# Sheet1.net
KiCad netlist of a schematic drawn in Altium Designer
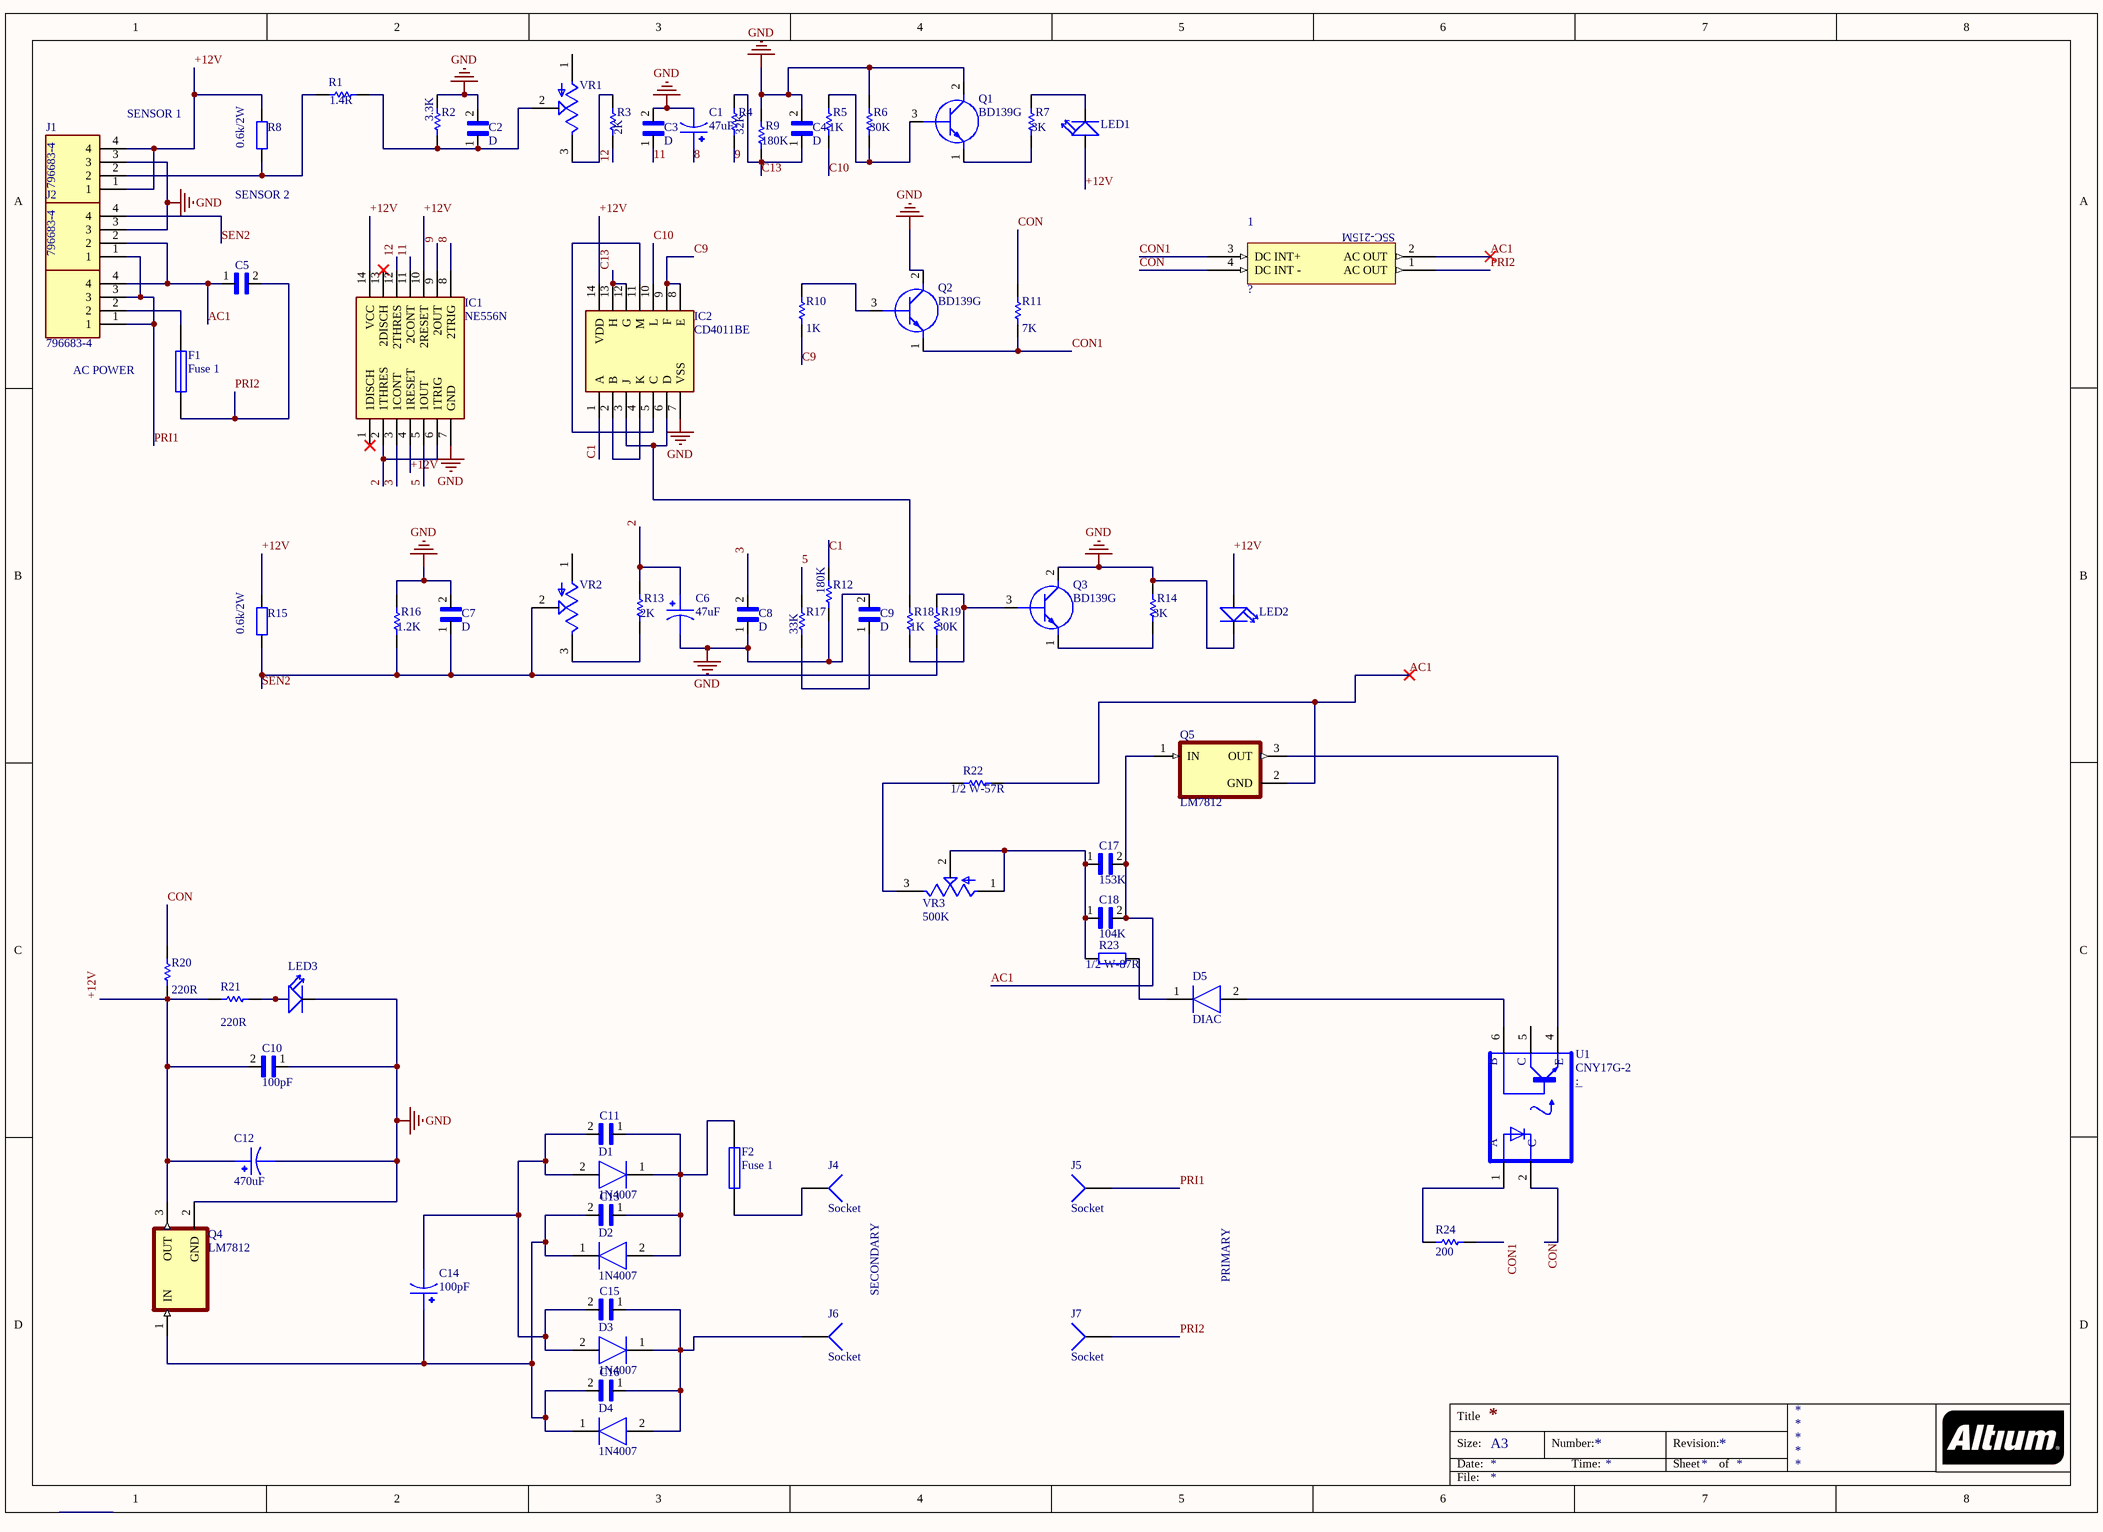
[diagram p0: Sheet1.SchDoc]

(export (version "E")
  (design (tool "Eeschema 10.0.6"))
  (components
    (comp (ref "1")
      (value "?")
      (footprint "PCBComponent_1")
      (libsource (lib "s5C-215M") (part "Component_1"))
    )
    (comp (ref "C1")
      (value "47uF")
      (footprint "CAPPRD500W60D1330H2700")
      (description "4700ÂµF 10V Aluminum Electrolytic Capacitors Radial, Can 98.8mOhm @ 120Hz 2000 Hrs @ 85Â°C")
      (fields (field (name "MP") "478CKS010M") (field (name "MF") "Illinois Capacitor"))
      (libsource (lib "new polar CAP 3D") (part "478CKS010M"))
    )
    (comp (ref "C2")
      (value "D")
      (footprint "CAP_DE21XSA100KN3AY02F")
      (fields (field (name "MP") "DE21XSA100KN3AY02F"))
      (libsource (lib "nonpolar capacitor square 3D") (part "DE21XSA100KN3AY02F"))
    )
    (comp (ref "C3")
      (value "D")
      (footprint "CAP_DE21XSA100KN3AY02F")
      (fields (field (name "MP") "DE21XSA100KN3AY02F"))
      (libsource (lib "nonpolar capacitor square 3D") (part "DE21XSA100KN3AY02F"))
    )
    (comp (ref "C4")
      (value "D")
      (footprint "CAP_DE21XSA100KN3AY02F")
      (fields (field (name "MP") "DE21XSA100KN3AY02F"))
      (libsource (lib "nonpolar capacitor square 3D") (part "DE21XSA100KN3AY02F"))
    )
    (comp (ref "C5")
      (value "~")
      (footprint "CAP_DE21XSA100KN3AY02F")
      (fields (field (name "MP") "DE21XSA100KN3AY02F"))
      (libsource (lib "nonpolar capacitor round 3D") (part "DE21XSA100KN3AY02F"))
    )
    (comp (ref "C6")
      (value "47uF")
      (footprint "CAPPRD500W60D1330H2700")
      (description "4700ÂµF 10V Aluminum Electrolytic Capacitors Radial, Can 98.8mOhm @ 120Hz 2000 Hrs @ 85Â°C")
      (fields (field (name "MP") "478CKS010M") (field (name "MF") "Illinois Capacitor"))
      (libsource (lib "") (part "478CKS010M_1"))
    )
    (comp (ref "C7")
      (value "D")
      (footprint "CAP_DE21XSA100KN3AY02F")
      (fields (field (name "MP") "DE21XSA100KN3AY02F"))
      (libsource (lib "nonpolar capacitor square 3D") (part "DE21XSA100KN3AY02F"))
    )
    (comp (ref "C8")
      (value "D")
      (footprint "CAP_DE21XSA100KN3AY02F")
      (fields (field (name "MP") "DE21XSA100KN3AY02F"))
      (libsource (lib "nonpolar capacitor square 3D") (part "DE21XSA100KN3AY02F"))
    )
    (comp (ref "C9")
      (value "D")
      (footprint "CAP_DE21XSA100KN3AY02F")
      (fields (field (name "MP") "DE21XSA100KN3AY02F"))
      (libsource (lib "nonpolar capacitor square 3D") (part "DE21XSA100KN3AY02F"))
    )
    (comp (ref "C10")
      (value "100pF")
      (footprint "CAP_DE21XSA100KN3AY02F")
      (fields (field (name "MP") "DE21XSA100KN3AY02F"))
      (libsource (lib "") (part "DE21XSA100KN3AY02F_1"))
    )
    (comp (ref "C11")
      (value "~")
      (footprint "CAP_DE21XSA100KN3AY02F")
      (fields (field (name "MP") "DE21XSA100KN3AY02F"))
      (libsource (lib "") (part "DE21XSA100KN3AY02F_1"))
    )
    (comp (ref "C12")
      (value "470uF")
      (footprint "CAPPRD500W60D1330H2700")
      (description "4700ÂµF 10V Aluminum Electrolytic Capacitors Radial, Can 98.8mOhm @ 120Hz 2000 Hrs @ 85Â°C")
      (fields (field (name "MP") "478CKS010M") (field (name "MF") "Illinois Capacitor"))
      (libsource (lib "CAP") (part "478CKS010M"))
    )
    (comp (ref "C13")
      (value "~")
      (footprint "CAP_DE21XSA100KN3AY02F")
      (fields (field (name "MP") "DE21XSA100KN3AY02F"))
      (libsource (lib "") (part "DE21XSA100KN3AY02F_1"))
    )
    (comp (ref "C14")
      (value "100pF")
      (footprint "CAPPRD500W60D1330H2700")
      (description "4700ÂµF 10V Aluminum Electrolytic Capacitors Radial, Can 98.8mOhm @ 120Hz 2000 Hrs @ 85Â°C")
      (fields (field (name "MP") "478CKS010M") (field (name "MF") "Illinois Capacitor"))
      (libsource (lib "new polar CAP 3D") (part "478CKS010M"))
    )
    (comp (ref "C15")
      (value "~")
      (footprint "CAP_DE21XSA100KN3AY02F")
      (fields (field (name "MP") "DE21XSA100KN3AY02F"))
      (libsource (lib "") (part "DE21XSA100KN3AY02F_1"))
    )
    (comp (ref "C16")
      (value "~")
      (footprint "CAP_DE21XSA100KN3AY02F")
      (fields (field (name "MP") "DE21XSA100KN3AY02F"))
      (libsource (lib "") (part "DE21XSA100KN3AY02F_1"))
    )
    (comp (ref "C17")
      (value "153K")
      (footprint "CAP_DE21XSA100KN3AY02F")
      (fields (field (name "MP") "DE21XSA100KN3AY02F"))
      (libsource (lib "") (part "DE21XSA100KN3AY02F_1"))
    )
    (comp (ref "C18")
      (value "104K")
      (footprint "CAP_DE21XSA100KN3AY02F")
      (fields (field (name "MP") "DE21XSA100KN3AY02F"))
      (libsource (lib "") (part "DE21XSA100KN3AY02F_1"))
    )
    (comp (ref "D1")
      (value "1N4007")
      (footprint "DIOAD1138W56L406D183")
      (description "Diode")
      (fields (field (name "MANUFACTURER_PART_NUMBER") "1N4678 (DO35)"))
      (libsource (lib "diode with 3d model") (part "1N4678__DO35_"))
    )
    (comp (ref "D2")
      (value "1N4007")
      (footprint "DIOAD1138W56L406D183")
      (description "Diode")
      (fields (field (name "MANUFACTURER_PART_NUMBER") "1N4678 (DO35)"))
      (libsource (lib "diode with 3d model") (part "1N4678__DO35_"))
    )
    (comp (ref "D3")
      (value "1N4007")
      (footprint "DIOAD1138W56L406D183")
      (description "Diode")
      (fields (field (name "MANUFACTURER_PART_NUMBER") "1N4678 (DO35)"))
      (libsource (lib "diode with 3d model") (part "1N4678__DO35_"))
    )
    (comp (ref "D4")
      (value "1N4007")
      (footprint "DIOAD1138W56L406D183")
      (description "Diode")
      (fields (field (name "MANUFACTURER_PART_NUMBER") "1N4678 (DO35)"))
      (libsource (lib "diode with 3d model") (part "1N4678__DO35_"))
    )
    (comp (ref "D5")
      (value "DIAC")
      (footprint "DIOAD1138W56L406D183")
      (description "Diode")
      (fields (field (name "MANUFACTURER_PART_NUMBER") "1N4678 (DO35)"))
      (libsource (lib "diode with 3d model") (part "1N4678__DO35_"))
    )
    (comp (ref "F1")
      (value "Fuse 1")
      (footprint "PIN-W2/E2.8")
      (description "Fuse")
      (fields (field (name "PUBLISHER") "Altium Limited"))
      (libsource (lib "Miscellaneous Devices") (part "Fuse 1"))
    )
    (comp (ref "F2")
      (value "Fuse 1")
      (footprint "PIN-W2/E2.8")
      (description "Fuse")
      (fields (field (name "PUBLISHER") "Altium Limited"))
      (libsource (lib "Miscellaneous Devices") (part "Fuse 1"))
    )
    (comp (ref "IC1")
      (value "NE556N")
      (footprint "DIP794W53P254L1930H508Q14N")
      (description "Integrated Circuit")
      (fields (field (name "MOUSER PART NUMBER") "595-NE556N"))
      (libsource (lib "NE556") (part "NE556N"))
    )
    (comp (ref "IC2")
      (value "CD4011BE")
      (footprint "SamacSys:DIP794W53P254L1930H508Q14N")
      (description "Integrated Circuit")
      (fields (field (name "MOUSER PART NUMBER") "595-CD4011BE"))
      (libsource (lib "CD4011") (part "CD4011BE"))
    )
    (comp (ref "J1")
      (value "796683-4")
      (footprint "TE_796683-4")
      (description "TERMI-BLOK PCB MOUNT 90 4P.")
      (fields (field (name "MF") "TE Connectivity"))
      (libsource (lib "4pin terminal 3D") (part "796683-4"))
    )
    (comp (ref "J2")
      (value "796683-4")
      (footprint "TE_796683-4")
      (description "TERMI-BLOK PCB MOUNT 90 4P.")
      (fields (field (name "MF") "TE Connectivity"))
      (libsource (lib "4pin terminal 3D") (part "796683-4"))
    )
    (comp (ref "J3")
      (value "796683-4")
      (footprint "TE_796683-4")
      (description "TERMI-BLOK PCB MOUNT 90 4P.")
      (fields (field (name "MF") "TE Connectivity"))
      (libsource (lib "4pin terminal 3D") (part "796683-4"))
    )
    (comp (ref "J4")
      (value "Socket")
      (footprint "PIN1")
      (fields (field (name "PUBLISHER") "Altium Limited"))
      (libsource (lib "Miscellaneous Connectors") (part "Socket"))
    )
    (comp (ref "J5")
      (value "Socket")
      (footprint "PIN1")
      (fields (field (name "PUBLISHER") "Altium Limited"))
      (libsource (lib "Miscellaneous Connectors") (part "Socket"))
    )
    (comp (ref "J6")
      (value "Socket")
      (footprint "PIN1")
      (fields (field (name "PUBLISHER") "Altium Limited"))
      (libsource (lib "Miscellaneous Connectors") (part "Socket"))
    )
    (comp (ref "J7")
      (value "Socket")
      (footprint "PIN1")
      (fields (field (name "PUBLISHER") "Altium Limited"))
      (libsource (lib "Miscellaneous Connectors") (part "Socket"))
    )
    (comp (ref "LED1")
      (value "~")
      (footprint "LED2-2.54-D10MM")
      (description "DIP LED Green-Vaporous Green-10mm")
      (fields (field (name "MF") "Chengguangxing") (field (name "MP") "G1004DC"))
      (libsource (lib "LED 3D") (part "DIP-LED-GREEN-VAPOROUS-GREEN-10MM(2P-D10MM)"))
    )
    (comp (ref "LED2")
      (value "~")
      (footprint "LED2-2.54-D10MM")
      (description "DIP LED Green-Vaporous Green-10mm")
      (fields (field (name "MF") "Chengguangxing") (field (name "MP") "G1004DC"))
      (libsource (lib "LED 3D") (part "DIP-LED-GREEN-VAPOROUS-GREEN-10MM(2P-D10MM)"))
    )
    (comp (ref "LED3")
      (value "~")
      (footprint "LED2-2.54-D10MM")
      (description "DIP LED Green-Vaporous Green-10mm")
      (fields (field (name "MF") "Chengguangxing") (field (name "MP") "G1004DC"))
      (libsource (lib "LED 3D") (part "DIP-LED-GREEN-VAPOROUS-GREEN-10MM(2P-D10MM)"))
    )
    (comp (ref "Q1")
      (value "BD139G")
      (footprint "TO229P300X760X1364-3P")
      (description "Transistor BJT NPN")
      (fields (field (name "MOUSER PART NUMBER") "863-BD139G"))
      (libsource (lib "BD139 NPN transistor") (part "BD139G"))
    )
    (comp (ref "Q2")
      (value "BD139G")
      (footprint "TO229P300X760X1364-3P")
      (description "Transistor BJT NPN")
      (fields (field (name "MOUSER PART NUMBER") "863-BD139G"))
      (libsource (lib "BD139 NPN transistor") (part "BD139G"))
    )
    (comp (ref "Q3")
      (value "BD139G")
      (footprint "TO229P300X760X1364-3P")
      (description "Transistor BJT NPN")
      (fields (field (name "MOUSER PART NUMBER") "863-BD139G"))
      (libsource (lib "BD139 NPN transistor") (part "BD139G"))
    )
    (comp (ref "Q4")
      (value "LM7812")
      (footprint "TO254P1054X470X2600-3")
      (description "Linear Voltage Regulator IC 1 Output 1A TO-220-3")
      (fields (field (name "MP") "LM7805CT") (field (name "MF") "ON Semiconductor"))
      (libsource (lib "") (part "LM7805CT/NOPB_1"))
    )
    (comp (ref "Q5")
      (value "LM7812")
      (footprint "TO254P1054X470X2600-3")
      (description "Linear Voltage Regulator IC 1 Output 1A TO-220-3")
      (fields (field (name "MP") "LM7805CT") (field (name "MF") "ON Semiconductor"))
      (libsource (lib "LM7805 3D") (part "LM7805CT/NOPB"))
    )
    (comp (ref "R1")
      (value "1.4R")
      (footprint "AXIAL-0.5")
      (description "Semiconductor Resistor")
      (fields (field (name "PUBLISHER") "Altium Limited"))
      (libsource (lib "Miscellaneous Devices") (part "Res Semi"))
    )
    (comp (ref "R2")
      (value "3.3K")
      (footprint "AXIAL-0.5")
      (description "Semiconductor Resistor")
      (fields (field (name "PUBLISHER") "Altium Limited"))
      (libsource (lib "Miscellaneous Devices") (part "Res Semi"))
    )
    (comp (ref "R3")
      (value "2K")
      (footprint "AXIAL-0.5")
      (description "Semiconductor Resistor")
      (fields (field (name "PUBLISHER") "Altium Limited"))
      (libsource (lib "Miscellaneous Devices") (part "Res Semi"))
    )
    (comp (ref "R4")
      (value "32K")
      (footprint "AXIAL-0.5")
      (description "Semiconductor Resistor")
      (fields (field (name "PUBLISHER") "Altium Limited"))
      (libsource (lib "Miscellaneous Devices") (part "Res Semi"))
    )
    (comp (ref "R5")
      (value "1K")
      (footprint "AXIAL-0.5")
      (description "Semiconductor Resistor")
      (fields (field (name "PUBLISHER") "Altium Limited"))
      (libsource (lib "Miscellaneous Devices") (part "Res Semi"))
    )
    (comp (ref "R6")
      (value "30K")
      (footprint "AXIAL-0.5")
      (description "Semiconductor Resistor")
      (fields (field (name "PUBLISHER") "Altium Limited"))
      (libsource (lib "Miscellaneous Devices") (part "Res Semi"))
    )
    (comp (ref "R7")
      (value "3K")
      (footprint "AXIAL-0.5")
      (description "Semiconductor Resistor")
      (fields (field (name "PUBLISHER") "Altium Limited"))
      (libsource (lib "Miscellaneous Devices") (part "Res Semi"))
    )
    (comp (ref "R8")
      (value "0.6k/2W")
      (footprint "AXIAL-0.4")
      (description "Resistor")
      (fields (field (name "PUBLISHER") "Altium Limited"))
      (libsource (lib "") (part "Res2_1"))
    )
    (comp (ref "R9")
      (value "180K")
      (footprint "AXIAL-0.5")
      (description "Semiconductor Resistor")
      (fields (field (name "PUBLISHER") "Altium Limited"))
      (libsource (lib "Miscellaneous Devices") (part "Res Semi"))
    )
    (comp (ref "R10")
      (value "1K")
      (footprint "AXIAL-0.5")
      (description "Semiconductor Resistor")
      (fields (field (name "PUBLISHER") "Altium Limited"))
      (libsource (lib "Miscellaneous Devices") (part "Res Semi"))
    )
    (comp (ref "R11")
      (value "7K")
      (footprint "AXIAL-0.5")
      (description "Semiconductor Resistor")
      (fields (field (name "PUBLISHER") "Altium Limited"))
      (libsource (lib "Miscellaneous Devices") (part "Res Semi"))
    )
    (comp (ref "R12")
      (value "180K")
      (footprint "AXIAL-0.5")
      (description "Semiconductor Resistor")
      (fields (field (name "PUBLISHER") "Altium Limited"))
      (libsource (lib "Miscellaneous Devices") (part "Res Semi"))
    )
    (comp (ref "R13")
      (value "2K")
      (footprint "AXIAL-0.5")
      (description "Semiconductor Resistor")
      (fields (field (name "PUBLISHER") "Altium Limited"))
      (libsource (lib "Miscellaneous Devices") (part "Res Semi"))
    )
    (comp (ref "R14")
      (value "3K")
      (footprint "AXIAL-0.5")
      (description "Semiconductor Resistor")
      (fields (field (name "PUBLISHER") "Altium Limited"))
      (libsource (lib "Miscellaneous Devices") (part "Res Semi"))
    )
    (comp (ref "R15")
      (value "0.6k/2W")
      (footprint "AXIAL-0.4")
      (description "Resistor")
      (fields (field (name "PUBLISHER") "Altium Limited"))
      (libsource (lib "") (part "Res2_1"))
    )
    (comp (ref "R16")
      (value "1.2K")
      (footprint "AXIAL-0.5")
      (description "Semiconductor Resistor")
      (fields (field (name "PUBLISHER") "Altium Limited"))
      (libsource (lib "Miscellaneous Devices") (part "Res Semi"))
    )
    (comp (ref "R17")
      (value "33K")
      (footprint "AXIAL-0.5")
      (description "Semiconductor Resistor")
      (fields (field (name "PUBLISHER") "Altium Limited"))
      (libsource (lib "Miscellaneous Devices") (part "Res Semi"))
    )
    (comp (ref "R18")
      (value "1K")
      (footprint "AXIAL-0.5")
      (description "Semiconductor Resistor")
      (fields (field (name "PUBLISHER") "Altium Limited"))
      (libsource (lib "Miscellaneous Devices") (part "Res Semi"))
    )
    (comp (ref "R19")
      (value "30K")
      (footprint "AXIAL-0.5")
      (description "Semiconductor Resistor")
      (fields (field (name "PUBLISHER") "Altium Limited"))
      (libsource (lib "Miscellaneous Devices") (part "Res Semi"))
    )
    (comp (ref "R20")
      (value "220R")
      (footprint "AXIAL-0.5")
      (description "Semiconductor Resistor")
      (fields (field (name "PUBLISHER") "Altium Limited"))
      (libsource (lib "Miscellaneous Devices") (part "Res Semi"))
    )
    (comp (ref "R21")
      (value "220R")
      (footprint "AXIAL-0.5")
      (description "Semiconductor Resistor")
      (fields (field (name "PUBLISHER") "Altium Limited"))
      (libsource (lib "Miscellaneous Devices") (part "Res Semi"))
    )
    (comp (ref "R22")
      (value "1/2 W-57R")
      (footprint "AXIAL-0.5")
      (description "Semiconductor Resistor")
      (fields (field (name "PUBLISHER") "Altium Limited"))
      (libsource (lib "Miscellaneous Devices") (part "Res Semi"))
    )
    (comp (ref "R23")
      (value "1/2 W-87R")
      (footprint "AXIAL-0.4")
      (description "Resistor")
      (fields (field (name "PUBLISHER") "Altium Limited"))
      (libsource (lib "Miscellaneous Devices") (part "Res2"))
    )
    (comp (ref "R24")
      (value "200")
      (footprint "AXIAL-0.5")
      (description "Semiconductor Resistor")
      (fields (field (name "PUBLISHER") "Altium Limited"))
      (libsource (lib "Miscellaneous Devices") (part "Res Semi"))
    )
    (comp (ref "U1")
      (value "CNY17G-2")
      (footprint "DIP762W50P254L730H410Q6")
      (description "Optoisolator Transistor with Base Output 5000Vrms 1 Channel 6-DIP")
      (fields (field (name "MF") "Vishay"))
      (libsource (lib "optocoupler 6 pin") (part "CNY17G-2"))
    )
    (comp (ref "VR1")
      (value "~")
      (footprint "TRIM_3362P-1-105")
      (description "1 MOhms 0.5W, 1/2W PC Pins Through Hole Trimmer Potentiometer Cermet 1 Turn Top Adjustment")
      (fields (field (name "MF") "Bourns") (field (name "MP") "3362P-1-105"))
      (libsource (lib "POT res 3D") (part "3362P-1-105"))
    )
    (comp (ref "VR2")
      (value "~")
      (footprint "TRIM_3362P-1-105")
      (description "1 MOhms 0.5W, 1/2W PC Pins Through Hole Trimmer Potentiometer Cermet 1 Turn Top Adjustment")
      (fields (field (name "MF") "Bourns") (field (name "MP") "3362P-1-105"))
      (libsource (lib "POT res 3D") (part "3362P-1-105"))
    )
    (comp (ref "VR3")
      (value "500K")
      (footprint "TRIM_3362P-1-105")
      (description "1 MOhms 0.5W, 1/2W PC Pins Through Hole Trimmer Potentiometer Cermet 1 Turn Top Adjustment")
      (fields (field (name "MF") "Bourns") (field (name "MP") "3362P-1-105"))
      (libsource (lib "POT res 3D") (part "3362P-1-105"))
    )
  )
  (nets
    (net (code "1") (name "/+12V") (class "Default")
      (node (ref "C10") (pin "2") (pinfunction "2_2") (pintype "passive"))
      (node (ref "C12") (pin "1") (pinfunction "1_1") (pintype "passive"))
      (node (ref "IC1") (pin "10") (pinfunction "2RESET_10") (pintype "passive"))
      (node (ref "IC1") (pin "14") (pinfunction "VCC_14") (pintype "passive"))
      (node (ref "IC1") (pin "4") (pinfunction "1RESET_4") (pintype "passive"))
      (node (ref "IC2") (pin "14") (pinfunction "VDD_14") (pintype "passive"))
      (node (ref "J1") (pin "1") (pinfunction "1_1") (pintype "passive"))
      (node (ref "J1") (pin "4") (pinfunction "4_4") (pintype "passive"))
      (node (ref "LED1") (pin "POS") (pinfunction "POS_POS") (pintype "passive"))
      (node (ref "LED2") (pin "POS") (pinfunction "POS_POS") (pintype "passive"))
      (node (ref "Q4") (pin "3") (pinfunction "OUT_3") (pintype "output"))
      (node (ref "R15") (pin "2") (pinfunction "2_2") (pintype "passive"))
      (node (ref "R20") (pin "2") (pinfunction "2_2") (pintype "passive"))
      (node (ref "R21") (pin "2") (pinfunction "2_2") (pintype "passive"))
      (node (ref "R8") (pin "2") (pinfunction "2_2") (pintype "passive"))
    )
    (net (code "2") (name "/2") (class "Default")
      (node (ref "C6") (pin "1") (pinfunction "1_1") (pintype "passive"))
      (node (ref "IC1") (pin "2") (pinfunction "1THRES_2") (pintype "passive"))
      (node (ref "IC1") (pin "6") (pinfunction "1TRIG_6") (pintype "passive"))
      (node (ref "R13") (pin "2") (pinfunction "2_2") (pintype "passive"))
    )
    (net (code "3") (name "/3") (class "Default")
      (node (ref "C8") (pin "2") (pinfunction "2_2") (pintype "passive"))
      (node (ref "IC1") (pin "3") (pinfunction "1CONT_3") (pintype "passive"))
    )
    (net (code "4") (name "/5") (class "Default")
      (node (ref "IC1") (pin "5") (pinfunction "1OUT_5") (pintype "passive"))
      (node (ref "R17") (pin "2") (pinfunction "2_2") (pintype "passive"))
    )
    (net (code "5") (name "/8") (class "Default")
      (node (ref "C1") (pin "1") (pinfunction "1_1") (pintype "passive"))
      (node (ref "IC1") (pin "8") (pinfunction "2TRIG_8") (pintype "passive"))
    )
    (net (code "6") (name "/9") (class "Default")
      (node (ref "IC1") (pin "9") (pinfunction "2OUT_9") (pintype "passive"))
      (node (ref "R4") (pin "1") (pinfunction "1_1") (pintype "passive"))
    )
    (net (code "7") (name "/11") (class "Default")
      (node (ref "C3") (pin "1") (pinfunction "1_1") (pintype "passive"))
      (node (ref "IC1") (pin "11") (pinfunction "2CONT_11") (pintype "passive"))
    )
    (net (code "8") (name "/12") (class "Default")
      (node (ref "IC1") (pin "12") (pinfunction "2THRES_12") (pintype "passive"))
      (node (ref "R3") (pin "1") (pinfunction "1_1") (pintype "passive"))
    )
    (net (code "9") (name "/AC1") (class "Default")
      (node (ref "1") (pin "2") (pinfunction "AC_OUT_2") (pintype "output"))
      (node (ref "C17") (pin "2") (pinfunction "2_2") (pintype "passive"))
      (node (ref "C18") (pin "2") (pinfunction "2_2") (pintype "passive"))
      (node (ref "C5") (pin "1") (pinfunction "1_1") (pintype "passive"))
      (node (ref "J2") (pin "2") (pinfunction "2_2") (pintype "passive"))
      (node (ref "J3") (pin "4") (pinfunction "4_4") (pintype "passive"))
      (node (ref "Q5") (pin "1") (pinfunction "IN_1") (pintype "input"))
      (node (ref "Q5") (pin "2") (pinfunction "GND_2") (pintype "power_in"))
      (node (ref "R22") (pin "2") (pinfunction "2_2") (pintype "passive"))
    )
    (net (code "10") (name "/C1") (class "Default")
      (node (ref "IC2") (pin "1") (pinfunction "A_1") (pintype "passive"))
      (node (ref "R12") (pin "2") (pinfunction "2_2") (pintype "passive"))
    )
    (net (code "11") (name "/C9") (class "Default")
      (node (ref "IC2") (pin "8") (pinfunction "E_8") (pintype "passive"))
      (node (ref "IC2") (pin "9") (pinfunction "F_9") (pintype "passive"))
      (node (ref "R10") (pin "1") (pinfunction "1_1") (pintype "passive"))
    )
    (net (code "12") (name "/C10") (class "Default")
      (node (ref "IC2") (pin "10") (pinfunction "L_10") (pintype "passive"))
      (node (ref "R5") (pin "1") (pinfunction "1_1") (pintype "passive"))
    )
    (net (code "13") (name "/C13") (class "Default")
      (node (ref "C4") (pin "1") (pinfunction "1_1") (pintype "passive"))
      (node (ref "IC2") (pin "12") (pinfunction "G_12") (pintype "passive"))
      (node (ref "IC2") (pin "13") (pinfunction "H_13") (pintype "passive"))
      (node (ref "R4") (pin "2") (pinfunction "2_2") (pintype "passive"))
      (node (ref "R9") (pin "1") (pinfunction "1_1") (pintype "passive"))
    )
    (net (code "14") (name "/CON") (class "Default")
      (node (ref "1") (pin "4") (pinfunction "DC_INT_-_4") (pintype "input"))
      (node (ref "R11") (pin "2") (pinfunction "2_2") (pintype "passive"))
      (node (ref "R20") (pin "1") (pinfunction "1_1") (pintype "passive"))
      (node (ref "U1") (pin "2") (pinfunction "C_2") (pintype "passive"))
    )
    (net (code "15") (name "/CON1") (class "Default")
      (node (ref "1") (pin "3") (pinfunction "DC_INT+_3") (pintype "input"))
      (node (ref "Q2") (pin "1") (pinfunction "E_1") (pintype "passive"))
      (node (ref "R11") (pin "1") (pinfunction "1_1") (pintype "passive"))
      (node (ref "R24") (pin "1") (pinfunction "1_1") (pintype "passive"))
    )
    (net (code "16") (name "/PRI1") (class "Default")
      (node (ref "J2") (pin "1") (pinfunction "1_1") (pintype "passive"))
      (node (ref "J3") (pin "1") (pinfunction "1_1") (pintype "passive"))
      (node (ref "J3") (pin "3") (pinfunction "3_3") (pintype "passive"))
      (node (ref "J5") (pin "1") (pinfunction "1_1") (pintype "passive"))
    )
    (net (code "17") (name "/PRI2") (class "Default")
      (node (ref "1") (pin "1") (pinfunction "AC_OUT_1") (pintype "output"))
      (node (ref "C5") (pin "2") (pinfunction "2_2") (pintype "passive"))
      (node (ref "F1") (pin "1") (pinfunction "1_1") (pintype "passive"))
      (node (ref "J7") (pin "1") (pinfunction "1_1") (pintype "passive"))
    )
    (net (code "18") (name "/SEN2") (class "Default")
      (node (ref "C7") (pin "1") (pinfunction "1_1") (pintype "passive"))
      (node (ref "J2") (pin "4") (pinfunction "4_4") (pintype "passive"))
      (node (ref "R15") (pin "1") (pinfunction "1_1") (pintype "passive"))
      (node (ref "R16") (pin "1") (pinfunction "1_1") (pintype "passive"))
      (node (ref "R19") (pin "1") (pinfunction "1_1") (pintype "passive"))
      (node (ref "VR2") (pin "2") (pinfunction "WIPER_2") (pintype "passive"))
    )
    (net (code "19") (name "GND") (class "Default")
      (node (ref "C1") (pin "2") (pinfunction "2_2") (pintype "passive"))
      (node (ref "C10") (pin "1") (pinfunction "1_1") (pintype "passive"))
      (node (ref "C12") (pin "2") (pinfunction "2_2") (pintype "passive"))
      (node (ref "C2") (pin "2") (pinfunction "2_2") (pintype "passive"))
      (node (ref "C3") (pin "2") (pinfunction "2_2") (pintype "passive"))
      (node (ref "C4") (pin "2") (pinfunction "2_2") (pintype "passive"))
      (node (ref "C6") (pin "2") (pinfunction "2_2") (pintype "passive"))
      (node (ref "C7") (pin "2") (pinfunction "2_2") (pintype "passive"))
      (node (ref "C8") (pin "1") (pinfunction "1_1") (pintype "passive"))
      (node (ref "C9") (pin "2") (pinfunction "2_2") (pintype "passive"))
      (node (ref "IC1") (pin "7") (pinfunction "GND_7") (pintype "passive"))
      (node (ref "IC2") (pin "7") (pinfunction "VSS_7") (pintype "passive"))
      (node (ref "J1") (pin "3") (pinfunction "3_3") (pintype "passive"))
      (node (ref "J2") (pin "3") (pinfunction "3_3") (pintype "passive"))
      (node (ref "LED2") (pin "NEG") (pinfunction "NEG_NEG") (pintype "passive"))
      (node (ref "LED3") (pin "NEG") (pinfunction "NEG_NEG") (pintype "passive"))
      (node (ref "Q1") (pin "2") (pinfunction "C_2") (pintype "passive"))
      (node (ref "Q2") (pin "2") (pinfunction "C_2") (pintype "passive"))
      (node (ref "Q3") (pin "2") (pinfunction "C_2") (pintype "passive"))
      (node (ref "Q4") (pin "2") (pinfunction "GND_2") (pintype "power_in"))
      (node (ref "R12") (pin "1") (pinfunction "1_1") (pintype "passive"))
      (node (ref "R14") (pin "2") (pinfunction "2_2") (pintype "passive"))
      (node (ref "R16") (pin "2") (pinfunction "2_2") (pintype "passive"))
      (node (ref "R2") (pin "2") (pinfunction "2_2") (pintype "passive"))
      (node (ref "R6") (pin "2") (pinfunction "2_2") (pintype "passive"))
      (node (ref "R9") (pin "2") (pinfunction "2_2") (pintype "passive"))
    )
    (net (code "20") (name "Net-(C9-Pad1)") (class "Default")
      (node (ref "C9") (pin "1") (pinfunction "1_1") (pintype "passive"))
      (node (ref "R17") (pin "1") (pinfunction "1_1") (pintype "passive"))
    )
    (net (code "21") (name "Net-(D1-A)") (class "Default")
      (node (ref "C11") (pin "2") (pinfunction "2_2") (pintype "passive"))
      (node (ref "C14") (pin "2") (pinfunction "2_2") (pintype "passive"))
      (node (ref "C15") (pin "2") (pinfunction "2_2") (pintype "passive"))
      (node (ref "D1") (pin "2") (pinfunction "A_2") (pintype "passive"))
      (node (ref "D3") (pin "2") (pinfunction "A_2") (pintype "passive"))
    )
    (net (code "22") (name "Net-(D1-K)") (class "Default")
      (node (ref "C11") (pin "1") (pinfunction "1_1") (pintype "passive"))
      (node (ref "C13") (pin "1") (pinfunction "1_1") (pintype "passive"))
      (node (ref "D1") (pin "1") (pinfunction "K_1") (pintype "passive"))
      (node (ref "D2") (pin "2") (pinfunction "A_2") (pintype "passive"))
      (node (ref "F2") (pin "2") (pinfunction "2_2") (pintype "passive"))
    )
    (net (code "23") (name "Net-(D2-K)") (class "Default")
      (node (ref "C13") (pin "2") (pinfunction "2_2") (pintype "passive"))
      (node (ref "C14") (pin "1") (pinfunction "1_1") (pintype "passive"))
      (node (ref "C16") (pin "2") (pinfunction "2_2") (pintype "passive"))
      (node (ref "D2") (pin "1") (pinfunction "K_1") (pintype "passive"))
      (node (ref "D4") (pin "1") (pinfunction "K_1") (pintype "passive"))
      (node (ref "Q4") (pin "1") (pinfunction "IN_1") (pintype "input"))
    )
    (net (code "24") (name "Net-(D3-K)") (class "Default")
      (node (ref "C15") (pin "1") (pinfunction "1_1") (pintype "passive"))
      (node (ref "C16") (pin "1") (pinfunction "1_1") (pintype "passive"))
      (node (ref "D3") (pin "1") (pinfunction "K_1") (pintype "passive"))
      (node (ref "D4") (pin "2") (pinfunction "A_2") (pintype "passive"))
      (node (ref "J6") (pin "1") (pinfunction "1_1") (pintype "passive"))
    )
    (net (code "25") (name "Net-(D5-A)") (class "Default")
      (node (ref "D5") (pin "2") (pinfunction "A_2") (pintype "passive"))
      (node (ref "U1") (pin "6") (pinfunction "B_6") (pintype "passive"))
    )
    (net (code "26") (name "Net-(D5-K)") (class "Default")
      (node (ref "D5") (pin "1") (pinfunction "K_1") (pintype "passive"))
      (node (ref "R23") (pin "2") (pinfunction "2_2") (pintype "passive"))
    )
    (net (code "27") (name "Net-(F1-Pad2)") (class "Default")
      (node (ref "F1") (pin "2") (pinfunction "2_2") (pintype "passive"))
      (node (ref "J3") (pin "2") (pinfunction "2_2") (pintype "passive"))
    )
    (net (code "28") (name "Net-(F2-Pad1)") (class "Default")
      (node (ref "F2") (pin "1") (pinfunction "1_1") (pintype "passive"))
      (node (ref "J4") (pin "1") (pinfunction "1_1") (pintype "passive"))
    )
    (net (code "29") (name "Net-(IC2-B)") (class "Default")
      (node (ref "IC2") (pin "2") (pinfunction "B_2") (pintype "passive"))
      (node (ref "IC2") (pin "4") (pinfunction "K_4") (pintype "passive"))
    )
    (net (code "30") (name "Net-(IC2-C)") (class "Default")
      (node (ref "IC2") (pin "11") (pinfunction "M_11") (pintype "passive"))
      (node (ref "IC2") (pin "5") (pinfunction "C_5") (pintype "passive"))
    )
    (net (code "31") (name "Net-(IC2-D)") (class "Default")
      (node (ref "IC2") (pin "3") (pinfunction "J_3") (pintype "passive"))
      (node (ref "IC2") (pin "6") (pinfunction "D_6") (pintype "passive"))
      (node (ref "R18") (pin "2") (pinfunction "2_2") (pintype "passive"))
    )
    (net (code "32") (name "Net-(J1-Pad2)") (class "Default")
      (node (ref "J1") (pin "2") (pinfunction "2_2") (pintype "passive"))
      (node (ref "R1") (pin "1") (pinfunction "1_1") (pintype "passive"))
      (node (ref "R8") (pin "1") (pinfunction "1_1") (pintype "passive"))
    )
    (net (code "33") (name "Net-(LED1-PadNEG)") (class "Default")
      (node (ref "LED1") (pin "NEG") (pinfunction "NEG_NEG") (pintype "passive"))
      (node (ref "R7") (pin "2") (pinfunction "2_2") (pintype "passive"))
    )
    (net (code "34") (name "Net-(LED3-PadPOS)") (class "Default")
      (node (ref "LED3") (pin "POS") (pinfunction "POS_POS") (pintype "passive"))
      (node (ref "R21") (pin "1") (pinfunction "1_1") (pintype "passive"))
    )
    (net (code "35") (name "Net-(Q1-B)") (class "Default")
      (node (ref "Q1") (pin "3") (pinfunction "B_3") (pintype "passive"))
      (node (ref "R5") (pin "2") (pinfunction "2_2") (pintype "passive"))
      (node (ref "R6") (pin "1") (pinfunction "1_1") (pintype "passive"))
    )
    (net (code "36") (name "Net-(Q1-E)") (class "Default")
      (node (ref "Q1") (pin "1") (pinfunction "E_1") (pintype "passive"))
      (node (ref "R7") (pin "1") (pinfunction "1_1") (pintype "passive"))
    )
    (net (code "37") (name "Net-(Q2-B)") (class "Default")
      (node (ref "Q2") (pin "3") (pinfunction "B_3") (pintype "passive"))
      (node (ref "R10") (pin "2") (pinfunction "2_2") (pintype "passive"))
    )
    (net (code "38") (name "Net-(Q3-B)") (class "Default")
      (node (ref "Q3") (pin "3") (pinfunction "B_3") (pintype "passive"))
      (node (ref "R18") (pin "1") (pinfunction "1_1") (pintype "passive"))
      (node (ref "R19") (pin "2") (pinfunction "2_2") (pintype "passive"))
    )
    (net (code "39") (name "Net-(Q3-E)") (class "Default")
      (node (ref "Q3") (pin "1") (pinfunction "E_1") (pintype "passive"))
      (node (ref "R14") (pin "1") (pinfunction "1_1") (pintype "passive"))
    )
    (net (code "40") (name "Net-(Q5-OUT)") (class "Default")
      (node (ref "Q5") (pin "3") (pinfunction "OUT_3") (pintype "output"))
      (node (ref "U1") (pin "4") (pinfunction "E_4") (pintype "passive"))
    )
    (net (code "41") (name "Net-(U1-A)") (class "Default")
      (node (ref "R24") (pin "2") (pinfunction "2_2") (pintype "passive"))
      (node (ref "U1") (pin "1") (pinfunction "A_1") (pintype "passive"))
    )
    (net (code "42") (name "Net-(VR1-CW)") (class "Default")
      (node (ref "R3") (pin "2") (pinfunction "2_2") (pintype "passive"))
      (node (ref "VR1") (pin "3") (pinfunction "CW_3") (pintype "passive"))
    )
    (net (code "43") (name "Net-(VR1-WIPER)") (class "Default")
      (node (ref "C2") (pin "1") (pinfunction "1_1") (pintype "passive"))
      (node (ref "R1") (pin "2") (pinfunction "2_2") (pintype "passive"))
      (node (ref "R2") (pin "1") (pinfunction "1_1") (pintype "passive"))
      (node (ref "VR1") (pin "2") (pinfunction "WIPER_2") (pintype "passive"))
    )
    (net (code "44") (name "Net-(VR2-CW)") (class "Default")
      (node (ref "R13") (pin "1") (pinfunction "1_1") (pintype "passive"))
      (node (ref "VR2") (pin "3") (pinfunction "CW_3") (pintype "passive"))
    )
    (net (code "45") (name "Net-(VR3-CCW)") (class "Default")
      (node (ref "C17") (pin "1") (pinfunction "1_1") (pintype "passive"))
      (node (ref "C18") (pin "1") (pinfunction "1_1") (pintype "passive"))
      (node (ref "R23") (pin "1") (pinfunction "1_1") (pintype "passive"))
      (node (ref "VR3") (pin "1") (pinfunction "CCW_1") (pintype "passive"))
      (node (ref "VR3") (pin "2") (pinfunction "WIPER_2") (pintype "passive"))
    )
    (net (code "46") (name "Net-(VR3-CW)") (class "Default")
      (node (ref "R22") (pin "1") (pinfunction "1_1") (pintype "passive"))
      (node (ref "VR3") (pin "3") (pinfunction "CW_3") (pintype "passive"))
    )
    (net (code "47") (name "unconnected-(IC1-1DISCH-Pad1)") (class "Default")
      (node (ref "IC1") (pin "1") (pinfunction "1DISCH_1") (pintype "passive+no_connect"))
    )
    (net (code "48") (name "unconnected-(IC1-2DISCH-Pad13)") (class "Default")
      (node (ref "IC1") (pin "13") (pinfunction "2DISCH_13") (pintype "passive+no_connect"))
    )
    (net (code "49") (name "unconnected-(U1-C`-Pad5)") (class "Default")
      (node (ref "U1") (pin "5") (pinfunction "C`_5") (pintype "passive"))
    )
    (net (code "50") (name "unconnected-(VR1-CCW-Pad1)") (class "Default")
      (node (ref "VR1") (pin "1") (pinfunction "CCW_1") (pintype "passive"))
    )
    (net (code "51") (name "unconnected-(VR2-CCW-Pad1)") (class "Default")
      (node (ref "VR2") (pin "1") (pinfunction "CCW_1") (pintype "passive"))
    )
  )
)
